# Sheet1.net
KiCad netlist of a schematic drawn in Altium Designer
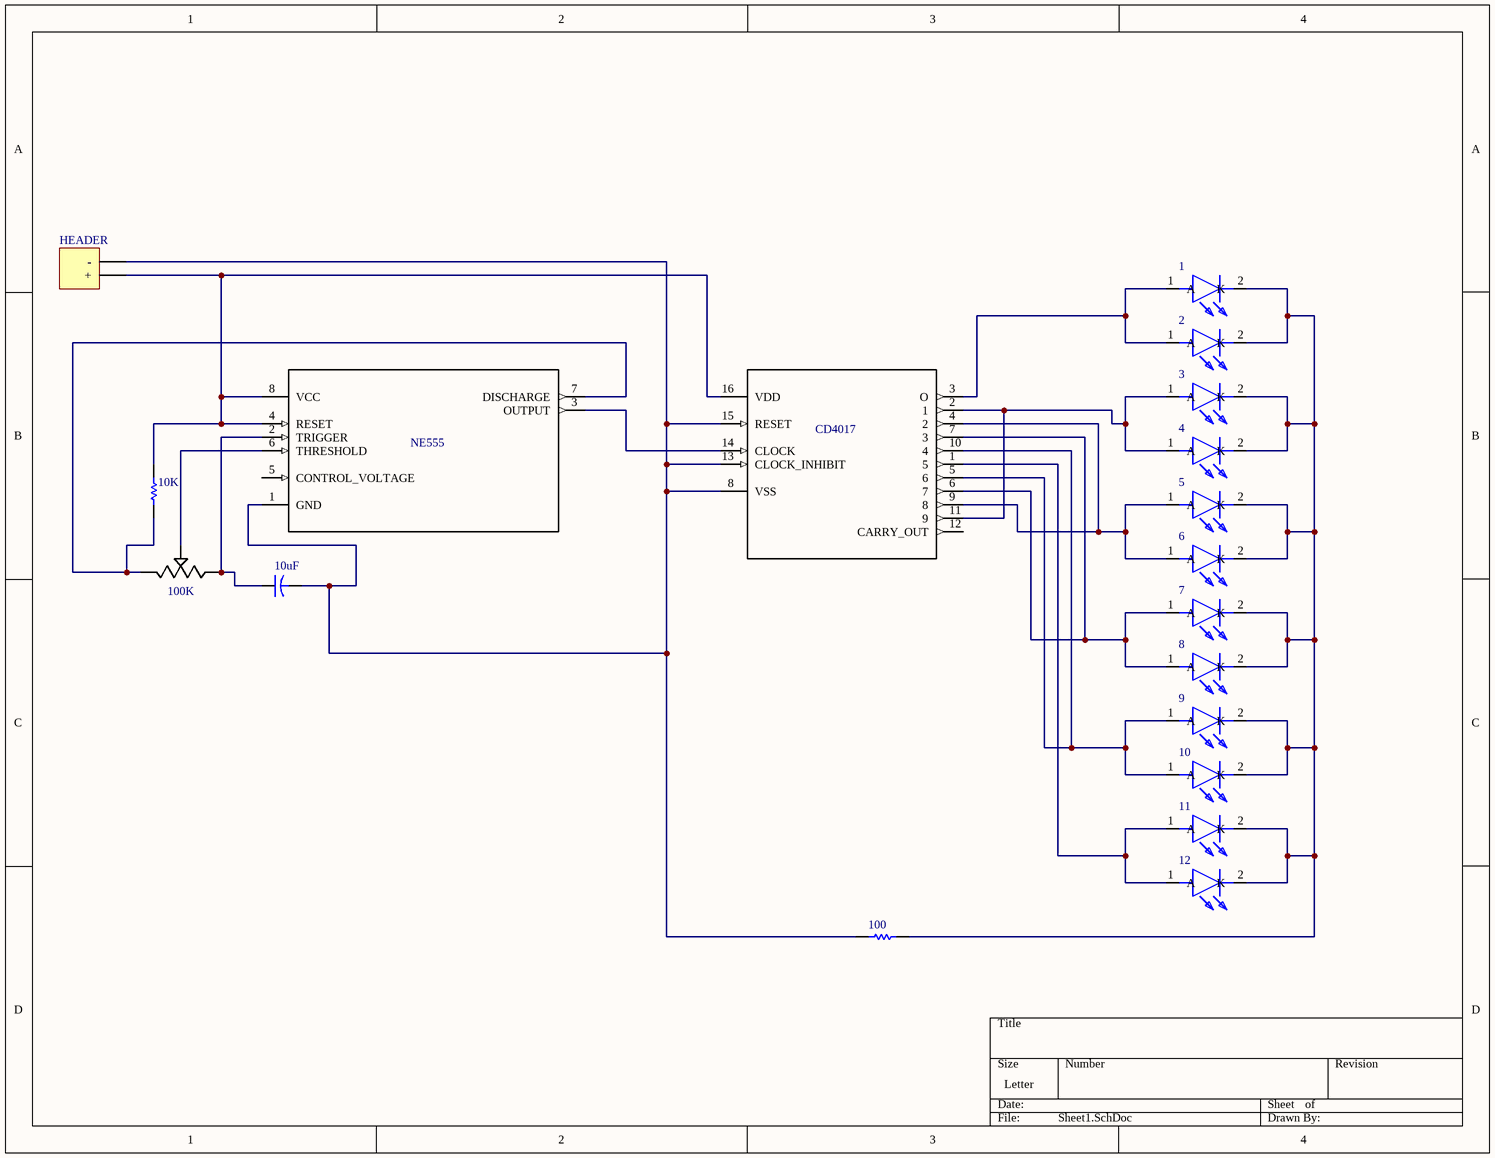
[diagram p0: Sheet1.SchDoc]

(export (version "E")
  (design (tool "Eeschema 10.0.6"))
  (components
    (comp (ref "1")
      (value "L-53GD")
      (footprint "SamacSys:L-53GD")
      (description "LED")
      (fields (field (name "RS PART NUMBER") "2286004A"))
      (libsource (lib "SamacSys") (part "L-53GD"))
    )
    (comp (ref "2")
      (value "L-53GD")
      (footprint "SamacSys:L-53GD")
      (description "LED")
      (fields (field (name "RS PART NUMBER") "2286004A"))
      (libsource (lib "SamacSys") (part "L-53GD"))
    )
    (comp (ref "3")
      (value "L-53GD")
      (footprint "SamacSys:L-53GD")
      (description "LED")
      (fields (field (name "RS PART NUMBER") "2286004A"))
      (libsource (lib "SamacSys") (part "L-53GD"))
    )
    (comp (ref "4")
      (value "L-53GD")
      (footprint "SamacSys:L-53GD")
      (description "LED")
      (fields (field (name "RS PART NUMBER") "2286004A"))
      (libsource (lib "SamacSys") (part "L-53GD"))
    )
    (comp (ref "5")
      (value "L-53GD")
      (footprint "SamacSys:L-53GD")
      (description "LED")
      (fields (field (name "RS PART NUMBER") "2286004A"))
      (libsource (lib "SamacSys") (part "L-53GD"))
    )
    (comp (ref "6")
      (value "L-53GD")
      (footprint "SamacSys:L-53GD")
      (description "LED")
      (fields (field (name "RS PART NUMBER") "2286004A"))
      (libsource (lib "SamacSys") (part "L-53GD"))
    )
    (comp (ref "7")
      (value "L-53GD")
      (footprint "SamacSys:L-53GD")
      (description "LED")
      (fields (field (name "RS PART NUMBER") "2286004A"))
      (libsource (lib "SamacSys") (part "L-53GD"))
    )
    (comp (ref "8")
      (value "L-53GD")
      (footprint "SamacSys:L-53GD")
      (description "LED")
      (fields (field (name "RS PART NUMBER") "2286004A"))
      (libsource (lib "SamacSys") (part "L-53GD"))
    )
    (comp (ref "9")
      (value "L-53GD")
      (footprint "SamacSys:L-53GD")
      (description "LED")
      (fields (field (name "RS PART NUMBER") "2286004A"))
      (libsource (lib "SamacSys") (part "L-53GD"))
    )
    (comp (ref "10")
      (value "L-53GD")
      (footprint "SamacSys:L-53GD")
      (description "LED")
      (fields (field (name "RS PART NUMBER") "2286004A"))
      (libsource (lib "SamacSys") (part "L-53GD"))
    )
    (comp (ref "10K")
      (value "Res1")
      (footprint "AXIAL-0.3")
      (description "Resistor")
      (fields (field (name "PUBLISHER") "Altium Limited"))
      (libsource (lib "Miscellaneous Devices") (part "Res1"))
    )
    (comp (ref "10uF")
      (value "Cap2")
      (footprint "CAPR5-4X5")
      (description "Capacitor")
      (fields (field (name "PUBLISHER") "Altium Limited"))
      (libsource (lib "Miscellaneous Devices") (part "Cap2"))
    )
    (comp (ref "11")
      (value "L-53GD")
      (footprint "SamacSys:L-53GD")
      (description "LED")
      (fields (field (name "RS PART NUMBER") "2286004A"))
      (libsource (lib "SamacSys") (part "L-53GD"))
    )
    (comp (ref "12")
      (value "L-53GD")
      (footprint "SamacSys:L-53GD")
      (description "LED")
      (fields (field (name "RS PART NUMBER") "2286004A"))
      (libsource (lib "SamacSys") (part "L-53GD"))
    )
    (comp (ref "100")
      (value "Res1")
      (footprint "AXIAL-0.3")
      (description "Resistor")
      (fields (field (name "PUBLISHER") "Altium Limited"))
      (libsource (lib "Miscellaneous Devices") (part "Res1"))
    )
    (comp (ref "100K")
      (value "EVN-D8AA03B14")
      (footprint "*TRIM_EVN-D8AA03B14")
      (description "Trimmer; Carbon; Rest 10 Kilohms; PCB; 1 Turn; Pwr-Rtg 0.1 W; Linear; Top Adj; 6 mm SQ")
      (fields (field (name "MF") "Panasonic Electronic"))
      (libsource (lib "EVN-D8AA03B14") (part "EVN-D8AA03B14"))
    )
    (comp (ref "CD4017")
      (value "CD4017BE")
      (footprint "*DIP254P762X508-16")
      (description "IC Mos 4017/CD4017BE HARRIS")
      (fields (field (name "MF") "Texas"))
      (libsource (lib "CD4017BE") (part "CD4017BE"))
    )
    (comp (ref "HEADER")
      (value "Header 2")
      (footprint "HDR1X2")
      (description "Header, 2-Pin")
      (fields (field (name "PUBLISHER") "Altium Limited"))
      (libsource (lib "Miscellaneous Connectors") (part "Header 2"))
    )
    (comp (ref "NE555")
      (value "NE555N")
      (footprint "*DIP254P762X533-8")
      (fields (field (name "MF") "ON Semiconductor"))
      (libsource (lib "NE555N") (part "NE555N"))
    )
  )
  (nets
    (net (code "1") (name "Net-(1-A)") (class "Default")
      (node (ref "1") (pin "1") (pinfunction "A_1") (pintype "passive"))
      (node (ref "2") (pin "1") (pinfunction "A_1") (pintype "passive"))
      (node (ref "CD4017") (pin "3") (pinfunction "O_3") (pintype "output"))
    )
    (net (code "2") (name "Net-(1-K)") (class "Default")
      (node (ref "1") (pin "2") (pinfunction "K_2") (pintype "passive"))
      (node (ref "10") (pin "2") (pinfunction "K_2") (pintype "passive"))
      (node (ref "100") (pin "2") (pinfunction "2_2") (pintype "passive"))
      (node (ref "11") (pin "2") (pinfunction "K_2") (pintype "passive"))
      (node (ref "12") (pin "2") (pinfunction "K_2") (pintype "passive"))
      (node (ref "2") (pin "2") (pinfunction "K_2") (pintype "passive"))
      (node (ref "3") (pin "2") (pinfunction "K_2") (pintype "passive"))
      (node (ref "4") (pin "2") (pinfunction "K_2") (pintype "passive"))
      (node (ref "5") (pin "2") (pinfunction "K_2") (pintype "passive"))
      (node (ref "6") (pin "2") (pinfunction "K_2") (pintype "passive"))
      (node (ref "7") (pin "2") (pinfunction "K_2") (pintype "passive"))
      (node (ref "8") (pin "2") (pinfunction "K_2") (pintype "passive"))
      (node (ref "9") (pin "2") (pinfunction "K_2") (pintype "passive"))
    )
    (net (code "3") (name "Net-(3-A)") (class "Default")
      (node (ref "3") (pin "1") (pinfunction "A_1") (pintype "passive"))
      (node (ref "4") (pin "1") (pinfunction "A_1") (pintype "passive"))
      (node (ref "CD4017") (pin "11") (pinfunction "9_11") (pintype "output"))
      (node (ref "CD4017") (pin "2") (pinfunction "1_2") (pintype "output"))
    )
    (net (code "4") (name "Net-(5-A)") (class "Default")
      (node (ref "5") (pin "1") (pinfunction "A_1") (pintype "passive"))
      (node (ref "6") (pin "1") (pinfunction "A_1") (pintype "passive"))
      (node (ref "CD4017") (pin "4") (pinfunction "2_4") (pintype "output"))
      (node (ref "CD4017") (pin "9") (pinfunction "8_9") (pintype "output"))
    )
    (net (code "5") (name "Net-(7-A)") (class "Default")
      (node (ref "7") (pin "1") (pinfunction "A_1") (pintype "passive"))
      (node (ref "8") (pin "1") (pinfunction "A_1") (pintype "passive"))
      (node (ref "CD4017") (pin "6") (pinfunction "7_6") (pintype "output"))
      (node (ref "CD4017") (pin "7") (pinfunction "3_7") (pintype "output"))
    )
    (net (code "6") (name "Net-(10-A)") (class "Default")
      (node (ref "10") (pin "1") (pinfunction "A_1") (pintype "passive"))
      (node (ref "9") (pin "1") (pinfunction "A_1") (pintype "passive"))
      (node (ref "CD4017") (pin "10") (pinfunction "4_10") (pintype "output"))
      (node (ref "CD4017") (pin "5") (pinfunction "6_5") (pintype "output"))
    )
    (net (code "7") (name "Net-(11-A)") (class "Default")
      (node (ref "11") (pin "1") (pinfunction "A_1") (pintype "passive"))
      (node (ref "12") (pin "1") (pinfunction "A_1") (pintype "passive"))
      (node (ref "CD4017") (pin "1") (pinfunction "5_1") (pintype "output"))
    )
    (net (code "8") (name "Net-(CD4017-CLOCK)") (class "Default")
      (node (ref "CD4017") (pin "14") (pinfunction "CLOCK_14") (pintype "input"))
      (node (ref "NE555") (pin "3") (pinfunction "OUTPUT_3") (pintype "output"))
    )
    (net (code "9") (name "Net-(CD4017-CLOCK_INHIBIT)") (class "Default")
      (node (ref "100") (pin "1") (pinfunction "1_1") (pintype "passive"))
      (node (ref "10uF") (pin "2") (pinfunction "2_2") (pintype "passive"))
      (node (ref "CD4017") (pin "13") (pinfunction "CLOCK_INHIBIT_13") (pintype "input"))
      (node (ref "CD4017") (pin "15") (pinfunction "RESET_15") (pintype "input"))
      (node (ref "CD4017") (pin "8") (pinfunction "VSS_8") (pintype "power_in"))
      (node (ref "HEADER") (pin "2") (pinfunction "-_2") (pintype "passive"))
      (node (ref "NE555") (pin "1") (pinfunction "GND_1") (pintype "passive"))
    )
    (net (code "10") (name "Net-(CD4017-VDD)") (class "Default")
      (node (ref "10K") (pin "2") (pinfunction "2_2") (pintype "passive"))
      (node (ref "CD4017") (pin "16") (pinfunction "VDD_16") (pintype "power_in"))
      (node (ref "HEADER") (pin "1") (pinfunction "+_1") (pintype "passive"))
      (node (ref "NE555") (pin "4") (pinfunction "RESET_4") (pintype "input"))
      (node (ref "NE555") (pin "8") (pinfunction "VCC_8") (pintype "power_in"))
    )
    (net (code "11") (name "Net-(NE555-DISCHARGE)") (class "Default")
      (node (ref "100K") (pin "3") (pinfunction "3_3") (pintype "passive"))
      (node (ref "10K") (pin "1") (pinfunction "1_1") (pintype "passive"))
      (node (ref "NE555") (pin "7") (pinfunction "DISCHARGE_7") (pintype "output"))
    )
    (net (code "12") (name "Net-(NE555-THRESHOLD)") (class "Default")
      (node (ref "100K") (pin "2") (pinfunction "2_2") (pintype "passive"))
      (node (ref "NE555") (pin "6") (pinfunction "THRESHOLD_6") (pintype "input"))
    )
    (net (code "13") (name "Net-(NE555-TRIGGER)") (class "Default")
      (node (ref "100K") (pin "1") (pinfunction "1_1") (pintype "passive"))
      (node (ref "10uF") (pin "1") (pinfunction "1_1") (pintype "passive"))
      (node (ref "NE555") (pin "2") (pinfunction "TRIGGER_2") (pintype "input"))
    )
    (net (code "14") (name "unconnected-(CD4017-CARRY_OUT-Pad12)") (class "Default")
      (node (ref "CD4017") (pin "12") (pinfunction "CARRY_OUT_12") (pintype "output"))
    )
    (net (code "15") (name "unconnected-(NE555-CONTROL_VOLTAGE-Pad5)") (class "Default")
      (node (ref "NE555") (pin "5") (pinfunction "CONTROL_VOLTAGE_5") (pintype "input"))
    )
  )
)
